# PCB_schematic.net
KiCad netlist of a schematic drawn in EAGLE
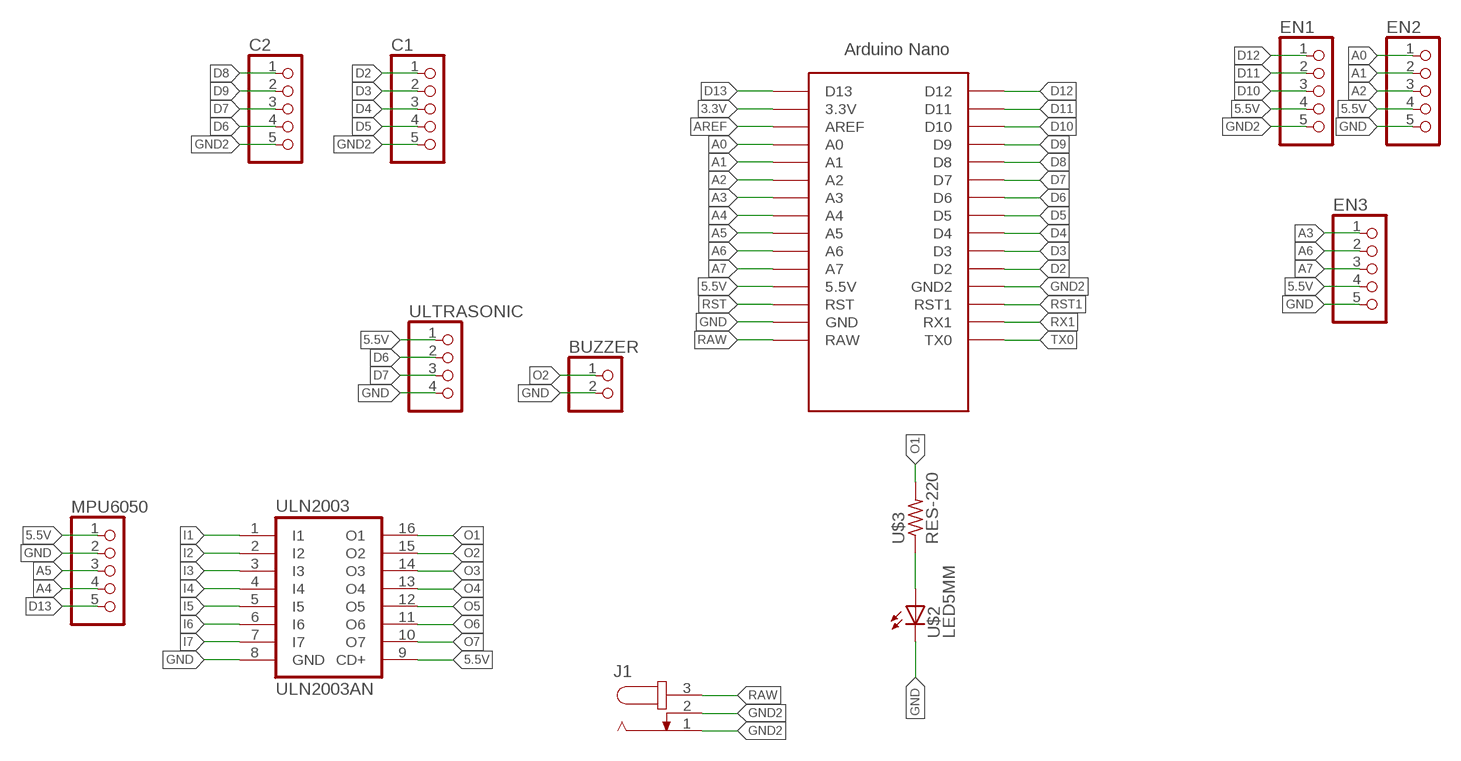
[diagram p0: schematic, sheet 1]

(export (version "E")
  (design (tool "Eeschema 10.0.6"))
  (components
    (comp (ref "BUZZER")
      (value "PINHD-1X2")
      (footprint "eagle-import:1X02")
      (libsource (lib "eagle-import") (part "PINHD-1X2"))
    )
    (comp (ref "C1")
      (value "PINHD-1X5")
      (footprint "eagle-import:1X05")
      (libsource (lib "eagle-import") (part "PINHD-1X5"))
    )
    (comp (ref "C2")
      (value "PINHD-1X5")
      (footprint "eagle-import:1X05")
      (libsource (lib "eagle-import") (part "PINHD-1X5"))
    )
    (comp (ref "EN1")
      (value "PINHD-1X5")
      (footprint "eagle-import:1X05")
      (libsource (lib "eagle-import") (part "PINHD-1X5"))
    )
    (comp (ref "EN2")
      (value "PINHD-1X5")
      (footprint "eagle-import:1X05")
      (libsource (lib "eagle-import") (part "PINHD-1X5"))
    )
    (comp (ref "EN3")
      (value "PINHD-1X5")
      (footprint "eagle-import:1X05")
      (libsource (lib "eagle-import") (part "PINHD-1X5"))
    )
    (comp (ref "J1")
      (value "JACK-PLUG0")
      (footprint "eagle-import:SPC4077")
      (libsource (lib "eagle-import") (part "JACK-PLUG0"))
    )
    (comp (ref "MPU6050")
      (value "PINHD-1X5")
      (footprint "eagle-import:1X05")
      (libsource (lib "eagle-import") (part "PINHD-1X5"))
    )
    (comp (ref "U$1")
      (value "ARDUINO_NANO")
      (footprint "eagle-import:NANO")
      (libsource (lib "eagle-import") (part "ARDUINO_NANO"))
    )
    (comp (ref "U$2")
      (value "LED5MM")
      (footprint "eagle-import:LED5MM")
      (libsource (lib "eagle-import") (part "LED5MM"))
    )
    (comp (ref "U$3")
      (value "RES-220")
      (footprint "eagle-import:0204_5")
      (libsource (lib "eagle-import") (part "RES-5"))
    )
    (comp (ref "ULN2003")
      (value "ULN2003AN")
      (footprint "eagle-import:DIL16")
      (libsource (lib "eagle-import") (part "ULN2003AN"))
    )
    (comp (ref "ULTRASONIC")
      (value "PINHD-1X4")
      (footprint "eagle-import:1X04")
      (libsource (lib "eagle-import") (part "PINHD-1X4"))
    )
  )
  (nets
    (net (code "1") (name "3.3V") (class "Default")
      (node (ref "U$1") (pin "3.3V") (pinfunction "3.3V_3.3V") (pintype "bidirectional"))
    )
    (net (code "2") (name "5.5V") (class "Default")
      (node (ref "EN1") (pin "4") (pinfunction "4_4") (pintype "passive"))
      (node (ref "EN2") (pin "4") (pinfunction "4_4") (pintype "passive"))
      (node (ref "EN3") (pin "4") (pinfunction "4_4") (pintype "passive"))
      (node (ref "MPU6050") (pin "1") (pinfunction "1_1") (pintype "passive"))
      (node (ref "U$1") (pin "5V") (pinfunction "5.5V_5V") (pintype "bidirectional"))
      (node (ref "ULN2003") (pin "9") (pinfunction "CD+_9") (pintype "passive"))
      (node (ref "ULTRASONIC") (pin "1") (pinfunction "1_1") (pintype "passive"))
    )
    (net (code "3") (name "A0") (class "Default")
      (node (ref "EN2") (pin "1") (pinfunction "1_1") (pintype "passive"))
      (node (ref "U$1") (pin "A0") (pinfunction "A0_A0") (pintype "bidirectional"))
    )
    (net (code "4") (name "A1") (class "Default")
      (node (ref "EN2") (pin "2") (pinfunction "2_2") (pintype "passive"))
      (node (ref "U$1") (pin "A1") (pinfunction "A1_A1") (pintype "bidirectional"))
    )
    (net (code "5") (name "A2") (class "Default")
      (node (ref "EN2") (pin "3") (pinfunction "3_3") (pintype "passive"))
      (node (ref "U$1") (pin "A2") (pinfunction "A2_A2") (pintype "bidirectional"))
    )
    (net (code "6") (name "A3") (class "Default")
      (node (ref "EN3") (pin "1") (pinfunction "1_1") (pintype "passive"))
      (node (ref "U$1") (pin "A3") (pinfunction "A3_A3") (pintype "bidirectional"))
    )
    (net (code "7") (name "A4") (class "Default")
      (node (ref "MPU6050") (pin "4") (pinfunction "4_4") (pintype "passive"))
      (node (ref "U$1") (pin "A4") (pinfunction "A4_A4") (pintype "bidirectional"))
    )
    (net (code "8") (name "A5") (class "Default")
      (node (ref "MPU6050") (pin "3") (pinfunction "3_3") (pintype "passive"))
      (node (ref "U$1") (pin "A5") (pinfunction "A5_A5") (pintype "bidirectional"))
    )
    (net (code "9") (name "A6") (class "Default")
      (node (ref "EN3") (pin "2") (pinfunction "2_2") (pintype "passive"))
      (node (ref "U$1") (pin "A6") (pinfunction "A6_A6") (pintype "bidirectional"))
    )
    (net (code "10") (name "A7") (class "Default")
      (node (ref "EN3") (pin "3") (pinfunction "3_3") (pintype "passive"))
      (node (ref "U$1") (pin "A7") (pinfunction "A7_A7") (pintype "bidirectional"))
    )
    (net (code "11") (name "AREF") (class "Default")
      (node (ref "U$1") (pin "AREF") (pinfunction "AREF_AREF") (pintype "bidirectional"))
    )
    (net (code "12") (name "D2") (class "Default")
      (node (ref "C1") (pin "1") (pinfunction "1_1") (pintype "passive"))
      (node (ref "U$1") (pin "D2") (pinfunction "D2_D2") (pintype "bidirectional"))
    )
    (net (code "13") (name "D3") (class "Default")
      (node (ref "C1") (pin "2") (pinfunction "2_2") (pintype "passive"))
      (node (ref "U$1") (pin "D3") (pinfunction "D3_D3") (pintype "bidirectional"))
    )
    (net (code "14") (name "D4") (class "Default")
      (node (ref "C1") (pin "3") (pinfunction "3_3") (pintype "passive"))
      (node (ref "U$1") (pin "D4") (pinfunction "D4_D4") (pintype "bidirectional"))
    )
    (net (code "15") (name "D5") (class "Default")
      (node (ref "C1") (pin "4") (pinfunction "4_4") (pintype "passive"))
      (node (ref "U$1") (pin "D5") (pinfunction "D5_D5") (pintype "bidirectional"))
    )
    (net (code "16") (name "D6") (class "Default")
      (node (ref "C2") (pin "4") (pinfunction "4_4") (pintype "passive"))
      (node (ref "U$1") (pin "D6") (pinfunction "D6_D6") (pintype "bidirectional"))
      (node (ref "ULTRASONIC") (pin "2") (pinfunction "2_2") (pintype "passive"))
    )
    (net (code "17") (name "D7") (class "Default")
      (node (ref "C2") (pin "3") (pinfunction "3_3") (pintype "passive"))
      (node (ref "U$1") (pin "D7") (pinfunction "D7_D7") (pintype "bidirectional"))
      (node (ref "ULTRASONIC") (pin "3") (pinfunction "3_3") (pintype "passive"))
    )
    (net (code "18") (name "D8") (class "Default")
      (node (ref "C2") (pin "1") (pinfunction "1_1") (pintype "passive"))
      (node (ref "U$1") (pin "D8") (pinfunction "D8_D8") (pintype "bidirectional"))
    )
    (net (code "19") (name "D9") (class "Default")
      (node (ref "C2") (pin "2") (pinfunction "2_2") (pintype "passive"))
      (node (ref "U$1") (pin "D9") (pinfunction "D9_D9") (pintype "bidirectional"))
    )
    (net (code "20") (name "D10") (class "Default")
      (node (ref "EN1") (pin "3") (pinfunction "3_3") (pintype "passive"))
      (node (ref "U$1") (pin "D10") (pinfunction "D10_D10") (pintype "bidirectional"))
    )
    (net (code "21") (name "D11") (class "Default")
      (node (ref "EN1") (pin "2") (pinfunction "2_2") (pintype "passive"))
      (node (ref "U$1") (pin "D11") (pinfunction "D11_D11") (pintype "bidirectional"))
    )
    (net (code "22") (name "D12") (class "Default")
      (node (ref "EN1") (pin "1") (pinfunction "1_1") (pintype "passive"))
      (node (ref "U$1") (pin "D12") (pinfunction "D12_D12") (pintype "bidirectional"))
    )
    (net (code "23") (name "D13") (class "Default")
      (node (ref "MPU6050") (pin "5") (pinfunction "5_5") (pintype "passive"))
      (node (ref "U$1") (pin "D13") (pinfunction "D13_D13") (pintype "bidirectional"))
    )
    (net (code "24") (name "GND") (class "Default")
      (node (ref "BUZZER") (pin "2") (pinfunction "2_2") (pintype "passive"))
      (node (ref "EN2") (pin "5") (pinfunction "5_5") (pintype "passive"))
      (node (ref "EN3") (pin "5") (pinfunction "5_5") (pintype "passive"))
      (node (ref "MPU6050") (pin "2") (pinfunction "2_2") (pintype "passive"))
      (node (ref "U$1") (pin "GND") (pinfunction "GND_GND") (pintype "bidirectional"))
      (node (ref "U$2") (pin "K") (pinfunction "C_K") (pintype "passive"))
      (node (ref "ULN2003") (pin "8") (pinfunction "GND_8") (pintype "power_in"))
      (node (ref "ULTRASONIC") (pin "4") (pinfunction "4_4") (pintype "passive"))
    )
    (net (code "25") (name "GND2") (class "Default")
      (node (ref "C1") (pin "5") (pinfunction "5_5") (pintype "passive"))
      (node (ref "C2") (pin "5") (pinfunction "5_5") (pintype "passive"))
      (node (ref "EN1") (pin "5") (pinfunction "5_5") (pintype "passive"))
      (node (ref "J1") (pin "1") (pinfunction "1_1") (pintype "passive"))
      (node (ref "J1") (pin "2") (pinfunction "2_2") (pintype "passive"))
      (node (ref "U$1") (pin "GND1") (pinfunction "GND2_GND1") (pintype "bidirectional"))
    )
    (net (code "26") (name "I1") (class "Default")
      (node (ref "ULN2003") (pin "1") (pinfunction "I1_1") (pintype "input"))
    )
    (net (code "27") (name "I2") (class "Default")
      (node (ref "ULN2003") (pin "2") (pinfunction "I2_2") (pintype "input"))
    )
    (net (code "28") (name "I3") (class "Default")
      (node (ref "ULN2003") (pin "3") (pinfunction "I3_3") (pintype "input"))
    )
    (net (code "29") (name "I4") (class "Default")
      (node (ref "ULN2003") (pin "4") (pinfunction "I4_4") (pintype "input"))
    )
    (net (code "30") (name "I5") (class "Default")
      (node (ref "ULN2003") (pin "5") (pinfunction "I5_5") (pintype "input"))
    )
    (net (code "31") (name "I6") (class "Default")
      (node (ref "ULN2003") (pin "6") (pinfunction "I6_6") (pintype "input"))
    )
    (net (code "32") (name "I7") (class "Default")
      (node (ref "ULN2003") (pin "7") (pinfunction "I7_7") (pintype "input"))
    )
    (net (code "33") (name "Net-(U$2-PadA)") (class "Default")
      (node (ref "U$2") (pin "A") (pinfunction "A_A") (pintype "passive"))
      (node (ref "U$3") (pin "1") (pinfunction "1_1") (pintype "passive"))
    )
    (net (code "34") (name "O1") (class "Default")
      (node (ref "U$3") (pin "2") (pinfunction "2_2") (pintype "passive"))
      (node (ref "ULN2003") (pin "16") (pinfunction "O1_16") (pintype "open_collector"))
    )
    (net (code "35") (name "O2") (class "Default")
      (node (ref "BUZZER") (pin "1") (pinfunction "1_1") (pintype "passive"))
      (node (ref "ULN2003") (pin "15") (pinfunction "O2_15") (pintype "open_collector"))
    )
    (net (code "36") (name "O3") (class "Default")
      (node (ref "ULN2003") (pin "14") (pinfunction "O3_14") (pintype "open_collector"))
    )
    (net (code "37") (name "O4") (class "Default")
      (node (ref "ULN2003") (pin "13") (pinfunction "O4_13") (pintype "open_collector"))
    )
    (net (code "38") (name "O5") (class "Default")
      (node (ref "ULN2003") (pin "12") (pinfunction "O5_12") (pintype "open_collector"))
    )
    (net (code "39") (name "O6") (class "Default")
      (node (ref "ULN2003") (pin "11") (pinfunction "O6_11") (pintype "open_collector"))
    )
    (net (code "40") (name "O7") (class "Default")
      (node (ref "ULN2003") (pin "10") (pinfunction "O7_10") (pintype "open_collector"))
    )
    (net (code "41") (name "RAW") (class "Default")
      (node (ref "J1") (pin "3") (pinfunction "3_3") (pintype "passive"))
      (node (ref "U$1") (pin "RAW") (pinfunction "RAW_RAW") (pintype "bidirectional"))
    )
    (net (code "42") (name "RST") (class "Default")
      (node (ref "U$1") (pin "RST") (pinfunction "RST_RST") (pintype "bidirectional"))
    )
    (net (code "43") (name "RST1") (class "Default")
      (node (ref "U$1") (pin "RST1") (pinfunction "RST1_RST1") (pintype "bidirectional"))
    )
    (net (code "44") (name "RX1") (class "Default")
      (node (ref "U$1") (pin "RX1") (pinfunction "RX1_RX1") (pintype "bidirectional"))
    )
    (net (code "45") (name "TX0") (class "Default")
      (node (ref "U$1") (pin "TX0") (pinfunction "TX0_TX0") (pintype "bidirectional"))
    )
  )
)
